# side.net
KiCad netlist of a schematic drawn in EAGLE
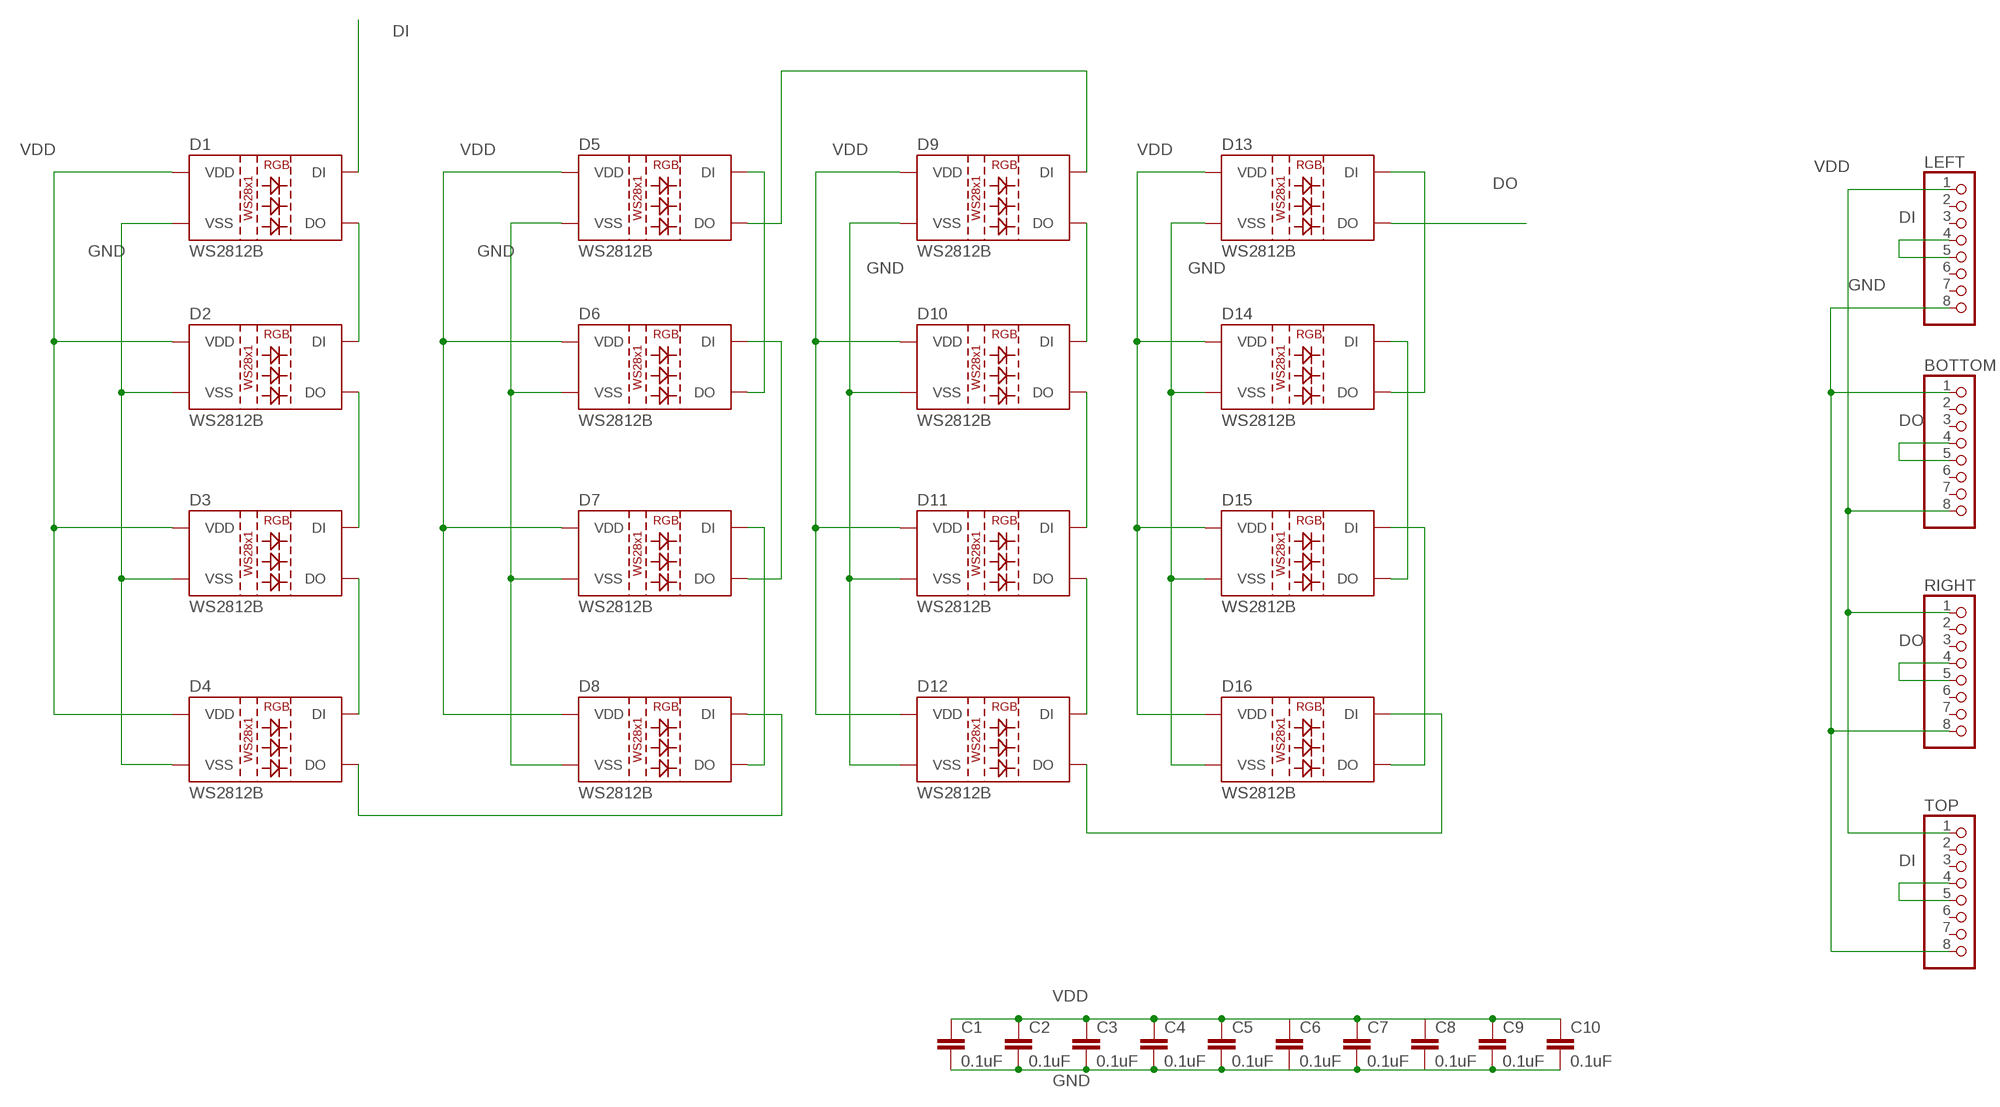
[diagram p0: schematic, sheet 1]

(export (version "E")
  (design (tool "Eeschema 10.0.6"))
  (components
    (comp (ref "BOTTOM")
      (value "PINHD-1X8")
      (footprint "eagle-import:1X08")
      (libsource (lib "eagle-import") (part "PINHD-1X8"))
    )
    (comp (ref "C1")
      (value "0.1uF")
      (footprint "eagle-import:0603")
      (libsource (lib "eagle-import") (part "0.1UF-0603-25V-5%"))
    )
    (comp (ref "C2")
      (value "0.1uF")
      (footprint "eagle-import:0603")
      (libsource (lib "eagle-import") (part "0.1UF-0603-25V-5%"))
    )
    (comp (ref "C3")
      (value "0.1uF")
      (footprint "eagle-import:0603")
      (libsource (lib "eagle-import") (part "0.1UF-0603-25V-5%"))
    )
    (comp (ref "C4")
      (value "0.1uF")
      (footprint "eagle-import:0603")
      (libsource (lib "eagle-import") (part "0.1UF-0603-25V-5%"))
    )
    (comp (ref "C5")
      (value "0.1uF")
      (footprint "eagle-import:0603")
      (libsource (lib "eagle-import") (part "0.1UF-0603-25V-5%"))
    )
    (comp (ref "C6")
      (value "0.1uF")
      (footprint "eagle-import:0603")
      (libsource (lib "eagle-import") (part "0.1UF-0603-25V-5%"))
    )
    (comp (ref "C7")
      (value "0.1uF")
      (footprint "eagle-import:0603")
      (libsource (lib "eagle-import") (part "0.1UF-0603-25V-5%"))
    )
    (comp (ref "C8")
      (value "0.1uF")
      (footprint "eagle-import:0603")
      (libsource (lib "eagle-import") (part "0.1UF-0603-25V-5%"))
    )
    (comp (ref "C9")
      (value "0.1uF")
      (footprint "eagle-import:0603")
      (libsource (lib "eagle-import") (part "0.1UF-0603-25V-5%"))
    )
    (comp (ref "C10")
      (value "0.1uF")
      (footprint "eagle-import:0603")
      (libsource (lib "eagle-import") (part "0.1UF-0603-25V-5%"))
    )
    (comp (ref "D1")
      (value "WS2812B")
      (footprint "eagle-import:WS2812B")
      (libsource (lib "eagle-import") (part "WS2812B"))
    )
    (comp (ref "D2")
      (value "WS2812B")
      (footprint "eagle-import:WS2812B")
      (libsource (lib "eagle-import") (part "WS2812B"))
    )
    (comp (ref "D3")
      (value "WS2812B")
      (footprint "eagle-import:WS2812B")
      (libsource (lib "eagle-import") (part "WS2812B"))
    )
    (comp (ref "D4")
      (value "WS2812B")
      (footprint "eagle-import:WS2812B")
      (libsource (lib "eagle-import") (part "WS2812B"))
    )
    (comp (ref "D5")
      (value "WS2812B")
      (footprint "eagle-import:WS2812B")
      (libsource (lib "eagle-import") (part "WS2812B"))
    )
    (comp (ref "D6")
      (value "WS2812B")
      (footprint "eagle-import:WS2812B")
      (libsource (lib "eagle-import") (part "WS2812B"))
    )
    (comp (ref "D7")
      (value "WS2812B")
      (footprint "eagle-import:WS2812B")
      (libsource (lib "eagle-import") (part "WS2812B"))
    )
    (comp (ref "D8")
      (value "WS2812B")
      (footprint "eagle-import:WS2812B")
      (libsource (lib "eagle-import") (part "WS2812B"))
    )
    (comp (ref "D9")
      (value "WS2812B")
      (footprint "eagle-import:WS2812B")
      (libsource (lib "eagle-import") (part "WS2812B"))
    )
    (comp (ref "D10")
      (value "WS2812B")
      (footprint "eagle-import:WS2812B")
      (libsource (lib "eagle-import") (part "WS2812B"))
    )
    (comp (ref "D11")
      (value "WS2812B")
      (footprint "eagle-import:WS2812B")
      (libsource (lib "eagle-import") (part "WS2812B"))
    )
    (comp (ref "D12")
      (value "WS2812B")
      (footprint "eagle-import:WS2812B")
      (libsource (lib "eagle-import") (part "WS2812B"))
    )
    (comp (ref "D13")
      (value "WS2812B")
      (footprint "eagle-import:WS2812B")
      (libsource (lib "eagle-import") (part "WS2812B"))
    )
    (comp (ref "D14")
      (value "WS2812B")
      (footprint "eagle-import:WS2812B")
      (libsource (lib "eagle-import") (part "WS2812B"))
    )
    (comp (ref "D15")
      (value "WS2812B")
      (footprint "eagle-import:WS2812B")
      (libsource (lib "eagle-import") (part "WS2812B"))
    )
    (comp (ref "D16")
      (value "WS2812B")
      (footprint "eagle-import:WS2812B")
      (libsource (lib "eagle-import") (part "WS2812B"))
    )
    (comp (ref "LEFT")
      (value "PINHD-1X8")
      (footprint "eagle-import:1X08")
      (libsource (lib "eagle-import") (part "PINHD-1X8"))
    )
    (comp (ref "RIGHT")
      (value "PINHD-1X8")
      (footprint "eagle-import:1X08")
      (libsource (lib "eagle-import") (part "PINHD-1X8"))
    )
    (comp (ref "TOP")
      (value "PINHD-1X8")
      (footprint "eagle-import:1X08")
      (libsource (lib "eagle-import") (part "PINHD-1X8"))
    )
  )
  (nets
    (net (code "1") (name "/DI") (class "Default")
      (node (ref "D1") (pin "4") (pinfunction "DI_4") (pintype "bidirectional"))
      (node (ref "LEFT") (pin "4") (pinfunction "4_4") (pintype "passive"))
      (node (ref "LEFT") (pin "5") (pinfunction "5_5") (pintype "passive"))
      (node (ref "TOP") (pin "4") (pinfunction "4_4") (pintype "passive"))
      (node (ref "TOP") (pin "5") (pinfunction "5_5") (pintype "passive"))
    )
    (net (code "2") (name "/DO") (class "Default")
      (node (ref "BOTTOM") (pin "4") (pinfunction "4_4") (pintype "passive"))
      (node (ref "BOTTOM") (pin "5") (pinfunction "5_5") (pintype "passive"))
      (node (ref "D13") (pin "2") (pinfunction "DO_2") (pintype "bidirectional"))
      (node (ref "RIGHT") (pin "4") (pinfunction "4_4") (pintype "passive"))
      (node (ref "RIGHT") (pin "5") (pinfunction "5_5") (pintype "passive"))
    )
    (net (code "3") (name "/GND") (class "Default")
      (node (ref "BOTTOM") (pin "8") (pinfunction "8_8") (pintype "passive"))
      (node (ref "C1") (pin "2") (pinfunction "2_2") (pintype "passive"))
      (node (ref "C10") (pin "2") (pinfunction "2_2") (pintype "passive"))
      (node (ref "C2") (pin "2") (pinfunction "2_2") (pintype "passive"))
      (node (ref "C3") (pin "2") (pinfunction "2_2") (pintype "passive"))
      (node (ref "C4") (pin "2") (pinfunction "2_2") (pintype "passive"))
      (node (ref "C5") (pin "2") (pinfunction "2_2") (pintype "passive"))
      (node (ref "C6") (pin "2") (pinfunction "2_2") (pintype "passive"))
      (node (ref "C7") (pin "2") (pinfunction "2_2") (pintype "passive"))
      (node (ref "C8") (pin "2") (pinfunction "2_2") (pintype "passive"))
      (node (ref "C9") (pin "2") (pinfunction "2_2") (pintype "passive"))
      (node (ref "D1") (pin "3") (pinfunction "VSS_3") (pintype "bidirectional"))
      (node (ref "D10") (pin "3") (pinfunction "VSS_3") (pintype "bidirectional"))
      (node (ref "D11") (pin "3") (pinfunction "VSS_3") (pintype "bidirectional"))
      (node (ref "D12") (pin "3") (pinfunction "VSS_3") (pintype "bidirectional"))
      (node (ref "D13") (pin "3") (pinfunction "VSS_3") (pintype "bidirectional"))
      (node (ref "D14") (pin "3") (pinfunction "VSS_3") (pintype "bidirectional"))
      (node (ref "D15") (pin "3") (pinfunction "VSS_3") (pintype "bidirectional"))
      (node (ref "D16") (pin "3") (pinfunction "VSS_3") (pintype "bidirectional"))
      (node (ref "D2") (pin "3") (pinfunction "VSS_3") (pintype "bidirectional"))
      (node (ref "D3") (pin "3") (pinfunction "VSS_3") (pintype "bidirectional"))
      (node (ref "D4") (pin "3") (pinfunction "VSS_3") (pintype "bidirectional"))
      (node (ref "D5") (pin "3") (pinfunction "VSS_3") (pintype "bidirectional"))
      (node (ref "D6") (pin "3") (pinfunction "VSS_3") (pintype "bidirectional"))
      (node (ref "D7") (pin "3") (pinfunction "VSS_3") (pintype "bidirectional"))
      (node (ref "D8") (pin "3") (pinfunction "VSS_3") (pintype "bidirectional"))
      (node (ref "D9") (pin "3") (pinfunction "VSS_3") (pintype "bidirectional"))
      (node (ref "LEFT") (pin "1") (pinfunction "1_1") (pintype "passive"))
      (node (ref "RIGHT") (pin "1") (pinfunction "1_1") (pintype "passive"))
      (node (ref "TOP") (pin "1") (pinfunction "1_1") (pintype "passive"))
    )
    (net (code "4") (name "/VDD") (class "Default")
      (node (ref "BOTTOM") (pin "1") (pinfunction "1_1") (pintype "passive"))
      (node (ref "C1") (pin "1") (pinfunction "1_1") (pintype "passive"))
      (node (ref "C10") (pin "1") (pinfunction "1_1") (pintype "passive"))
      (node (ref "C2") (pin "1") (pinfunction "1_1") (pintype "passive"))
      (node (ref "C3") (pin "1") (pinfunction "1_1") (pintype "passive"))
      (node (ref "C4") (pin "1") (pinfunction "1_1") (pintype "passive"))
      (node (ref "C5") (pin "1") (pinfunction "1_1") (pintype "passive"))
      (node (ref "C6") (pin "1") (pinfunction "1_1") (pintype "passive"))
      (node (ref "C7") (pin "1") (pinfunction "1_1") (pintype "passive"))
      (node (ref "C8") (pin "1") (pinfunction "1_1") (pintype "passive"))
      (node (ref "C9") (pin "1") (pinfunction "1_1") (pintype "passive"))
      (node (ref "D1") (pin "1") (pinfunction "VDD_1") (pintype "bidirectional"))
      (node (ref "D10") (pin "1") (pinfunction "VDD_1") (pintype "bidirectional"))
      (node (ref "D11") (pin "1") (pinfunction "VDD_1") (pintype "bidirectional"))
      (node (ref "D12") (pin "1") (pinfunction "VDD_1") (pintype "bidirectional"))
      (node (ref "D13") (pin "1") (pinfunction "VDD_1") (pintype "bidirectional"))
      (node (ref "D14") (pin "1") (pinfunction "VDD_1") (pintype "bidirectional"))
      (node (ref "D15") (pin "1") (pinfunction "VDD_1") (pintype "bidirectional"))
      (node (ref "D16") (pin "1") (pinfunction "VDD_1") (pintype "bidirectional"))
      (node (ref "D2") (pin "1") (pinfunction "VDD_1") (pintype "bidirectional"))
      (node (ref "D3") (pin "1") (pinfunction "VDD_1") (pintype "bidirectional"))
      (node (ref "D4") (pin "1") (pinfunction "VDD_1") (pintype "bidirectional"))
      (node (ref "D5") (pin "1") (pinfunction "VDD_1") (pintype "bidirectional"))
      (node (ref "D6") (pin "1") (pinfunction "VDD_1") (pintype "bidirectional"))
      (node (ref "D7") (pin "1") (pinfunction "VDD_1") (pintype "bidirectional"))
      (node (ref "D8") (pin "1") (pinfunction "VDD_1") (pintype "bidirectional"))
      (node (ref "D9") (pin "1") (pinfunction "VDD_1") (pintype "bidirectional"))
      (node (ref "LEFT") (pin "8") (pinfunction "8_8") (pintype "passive"))
      (node (ref "RIGHT") (pin "8") (pinfunction "8_8") (pintype "passive"))
      (node (ref "TOP") (pin "8") (pinfunction "8_8") (pintype "passive"))
    )
    (net (code "5") (name "Net-(D1-DO)") (class "Default")
      (node (ref "D1") (pin "2") (pinfunction "DO_2") (pintype "bidirectional"))
      (node (ref "D2") (pin "4") (pinfunction "DI_4") (pintype "bidirectional"))
    )
    (net (code "6") (name "Net-(D2-DO)") (class "Default")
      (node (ref "D2") (pin "2") (pinfunction "DO_2") (pintype "bidirectional"))
      (node (ref "D3") (pin "4") (pinfunction "DI_4") (pintype "bidirectional"))
    )
    (net (code "7") (name "Net-(D3-DO)") (class "Default")
      (node (ref "D3") (pin "2") (pinfunction "DO_2") (pintype "bidirectional"))
      (node (ref "D4") (pin "4") (pinfunction "DI_4") (pintype "bidirectional"))
    )
    (net (code "8") (name "Net-(D4-DO)") (class "Default")
      (node (ref "D4") (pin "2") (pinfunction "DO_2") (pintype "bidirectional"))
      (node (ref "D8") (pin "4") (pinfunction "DI_4") (pintype "bidirectional"))
    )
    (net (code "9") (name "Net-(D5-DI)") (class "Default")
      (node (ref "D5") (pin "4") (pinfunction "DI_4") (pintype "bidirectional"))
      (node (ref "D6") (pin "2") (pinfunction "DO_2") (pintype "bidirectional"))
    )
    (net (code "10") (name "Net-(D5-DO)") (class "Default")
      (node (ref "D5") (pin "2") (pinfunction "DO_2") (pintype "bidirectional"))
      (node (ref "D9") (pin "4") (pinfunction "DI_4") (pintype "bidirectional"))
    )
    (net (code "11") (name "Net-(D6-DI)") (class "Default")
      (node (ref "D6") (pin "4") (pinfunction "DI_4") (pintype "bidirectional"))
      (node (ref "D7") (pin "2") (pinfunction "DO_2") (pintype "bidirectional"))
    )
    (net (code "12") (name "Net-(D7-DI)") (class "Default")
      (node (ref "D7") (pin "4") (pinfunction "DI_4") (pintype "bidirectional"))
      (node (ref "D8") (pin "2") (pinfunction "DO_2") (pintype "bidirectional"))
    )
    (net (code "13") (name "Net-(D10-DI)") (class "Default")
      (node (ref "D10") (pin "4") (pinfunction "DI_4") (pintype "bidirectional"))
      (node (ref "D9") (pin "2") (pinfunction "DO_2") (pintype "bidirectional"))
    )
    (net (code "14") (name "Net-(D10-DO)") (class "Default")
      (node (ref "D10") (pin "2") (pinfunction "DO_2") (pintype "bidirectional"))
      (node (ref "D11") (pin "4") (pinfunction "DI_4") (pintype "bidirectional"))
    )
    (net (code "15") (name "Net-(D11-DO)") (class "Default")
      (node (ref "D11") (pin "2") (pinfunction "DO_2") (pintype "bidirectional"))
      (node (ref "D12") (pin "4") (pinfunction "DI_4") (pintype "bidirectional"))
    )
    (net (code "16") (name "Net-(D12-DO)") (class "Default")
      (node (ref "D12") (pin "2") (pinfunction "DO_2") (pintype "bidirectional"))
      (node (ref "D16") (pin "4") (pinfunction "DI_4") (pintype "bidirectional"))
    )
    (net (code "17") (name "Net-(D13-DI)") (class "Default")
      (node (ref "D13") (pin "4") (pinfunction "DI_4") (pintype "bidirectional"))
      (node (ref "D14") (pin "2") (pinfunction "DO_2") (pintype "bidirectional"))
    )
    (net (code "18") (name "Net-(D14-DI)") (class "Default")
      (node (ref "D14") (pin "4") (pinfunction "DI_4") (pintype "bidirectional"))
      (node (ref "D15") (pin "2") (pinfunction "DO_2") (pintype "bidirectional"))
    )
    (net (code "19") (name "Net-(D15-DI)") (class "Default")
      (node (ref "D15") (pin "4") (pinfunction "DI_4") (pintype "bidirectional"))
      (node (ref "D16") (pin "2") (pinfunction "DO_2") (pintype "bidirectional"))
    )
    (net (code "20") (name "unconnected-(BOTTOM-Pad2)") (class "Default")
      (node (ref "BOTTOM") (pin "2") (pinfunction "2_2") (pintype "passive"))
    )
    (net (code "21") (name "unconnected-(BOTTOM-Pad3)") (class "Default")
      (node (ref "BOTTOM") (pin "3") (pinfunction "3_3") (pintype "passive"))
    )
    (net (code "22") (name "unconnected-(BOTTOM-Pad6)") (class "Default")
      (node (ref "BOTTOM") (pin "6") (pinfunction "6_6") (pintype "passive"))
    )
    (net (code "23") (name "unconnected-(BOTTOM-Pad7)") (class "Default")
      (node (ref "BOTTOM") (pin "7") (pinfunction "7_7") (pintype "passive"))
    )
    (net (code "24") (name "unconnected-(LEFT-Pad2)") (class "Default")
      (node (ref "LEFT") (pin "2") (pinfunction "2_2") (pintype "passive"))
    )
    (net (code "25") (name "unconnected-(LEFT-Pad3)") (class "Default")
      (node (ref "LEFT") (pin "3") (pinfunction "3_3") (pintype "passive"))
    )
    (net (code "26") (name "unconnected-(LEFT-Pad6)") (class "Default")
      (node (ref "LEFT") (pin "6") (pinfunction "6_6") (pintype "passive"))
    )
    (net (code "27") (name "unconnected-(LEFT-Pad7)") (class "Default")
      (node (ref "LEFT") (pin "7") (pinfunction "7_7") (pintype "passive"))
    )
    (net (code "28") (name "unconnected-(RIGHT-Pad2)") (class "Default")
      (node (ref "RIGHT") (pin "2") (pinfunction "2_2") (pintype "passive"))
    )
    (net (code "29") (name "unconnected-(RIGHT-Pad3)") (class "Default")
      (node (ref "RIGHT") (pin "3") (pinfunction "3_3") (pintype "passive"))
    )
    (net (code "30") (name "unconnected-(RIGHT-Pad6)") (class "Default")
      (node (ref "RIGHT") (pin "6") (pinfunction "6_6") (pintype "passive"))
    )
    (net (code "31") (name "unconnected-(RIGHT-Pad7)") (class "Default")
      (node (ref "RIGHT") (pin "7") (pinfunction "7_7") (pintype "passive"))
    )
    (net (code "32") (name "unconnected-(TOP-Pad2)") (class "Default")
      (node (ref "TOP") (pin "2") (pinfunction "2_2") (pintype "passive"))
    )
    (net (code "33") (name "unconnected-(TOP-Pad3)") (class "Default")
      (node (ref "TOP") (pin "3") (pinfunction "3_3") (pintype "passive"))
    )
    (net (code "34") (name "unconnected-(TOP-Pad6)") (class "Default")
      (node (ref "TOP") (pin "6") (pinfunction "6_6") (pintype "passive"))
    )
    (net (code "35") (name "unconnected-(TOP-Pad7)") (class "Default")
      (node (ref "TOP") (pin "7") (pinfunction "7_7") (pintype "passive"))
    )
  )
)
